# PDMschemE-Car2018.net
KiCad netlist of a schematic drawn in EAGLE
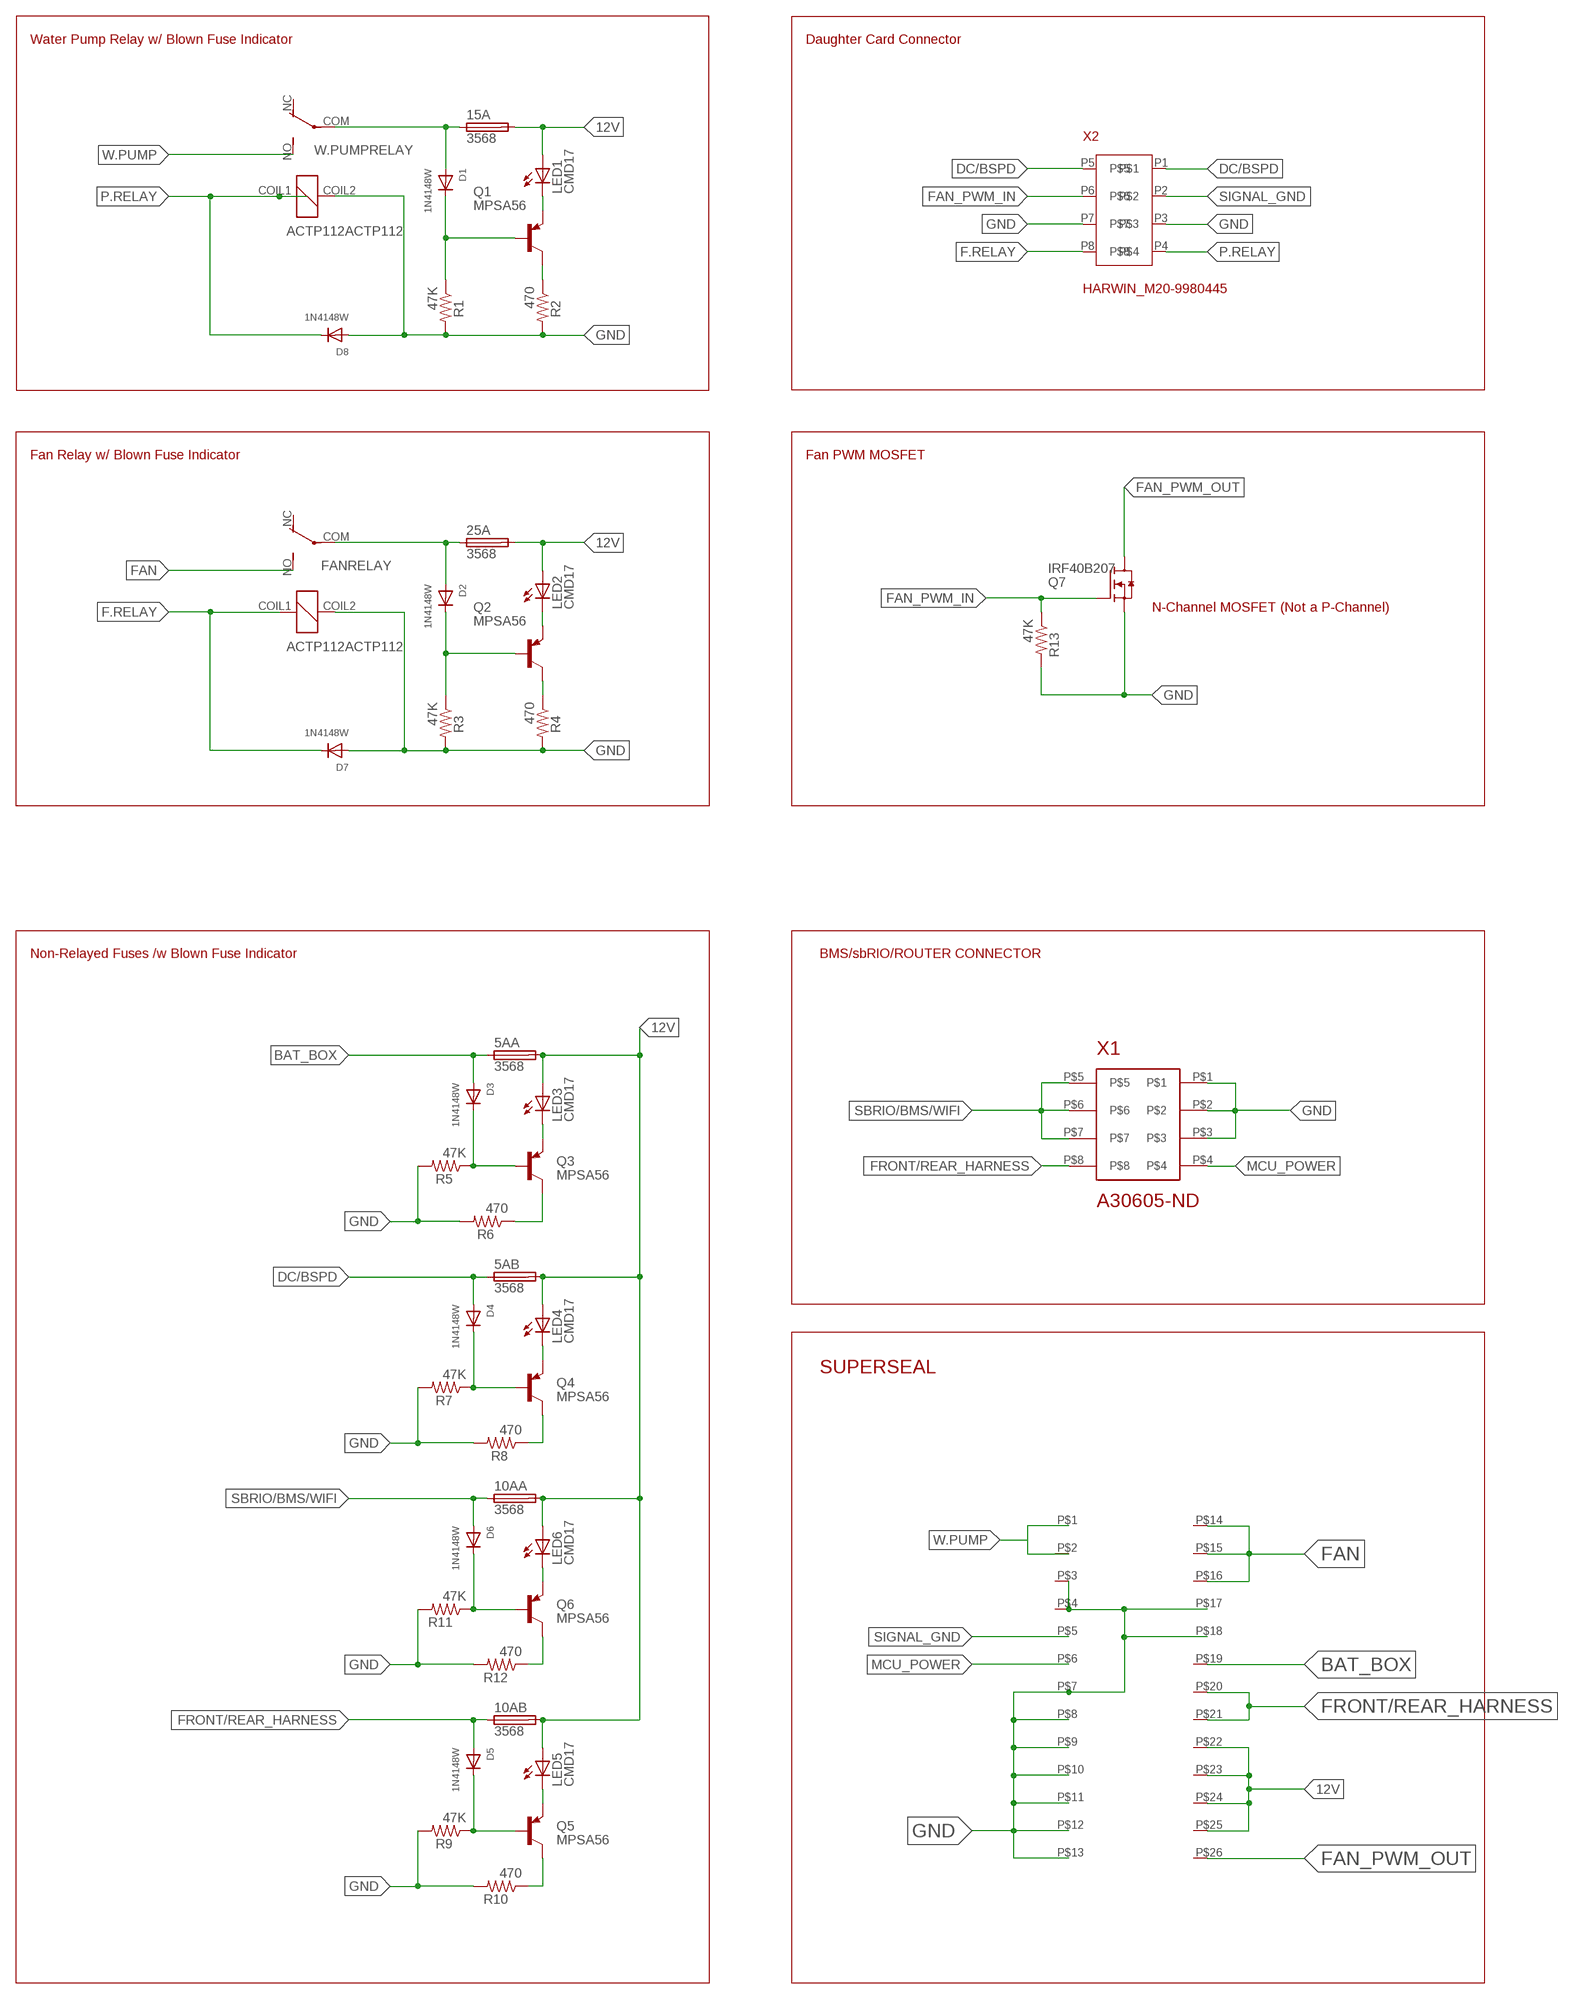
[diagram p0: schematic, sheet 1]

(export (version "E")
  (design (tool "Eeschema 10.0.6"))
  (components
    (comp (ref "5AA")
      (value "3568")
      (footprint "eagle-import:3568")
      (libsource (lib "eagle-import") (part "3568"))
    )
    (comp (ref "5AB")
      (value "3568")
      (footprint "eagle-import:3568")
      (libsource (lib "eagle-import") (part "3568"))
    )
    (comp (ref "10AA")
      (value "3568")
      (footprint "eagle-import:3568")
      (libsource (lib "eagle-import") (part "3568"))
    )
    (comp (ref "10AB")
      (value "3568")
      (footprint "eagle-import:3568")
      (libsource (lib "eagle-import") (part "3568"))
    )
    (comp (ref "15A")
      (value "3568")
      (footprint "eagle-import:3568")
      (libsource (lib "eagle-import") (part "3568"))
    )
    (comp (ref "25A")
      (value "3568")
      (footprint "eagle-import:3568")
      (libsource (lib "eagle-import") (part "3568"))
    )
    (comp (ref "D1")
      (value "1N4148W")
      (footprint "eagle-import:SOD-123")
      (libsource (lib "eagle-import") (part "DIODESOD-123"))
    )
    (comp (ref "D2")
      (value "1N4148W")
      (footprint "eagle-import:SOD-123")
      (libsource (lib "eagle-import") (part "DIODESOD-123"))
    )
    (comp (ref "D3")
      (value "1N4148W")
      (footprint "eagle-import:SOD-123")
      (libsource (lib "eagle-import") (part "DIODESOD-123"))
    )
    (comp (ref "D4")
      (value "1N4148W")
      (footprint "eagle-import:SOD-123")
      (libsource (lib "eagle-import") (part "DIODESOD-123"))
    )
    (comp (ref "D5")
      (value "1N4148W")
      (footprint "eagle-import:SOD-123")
      (libsource (lib "eagle-import") (part "DIODESOD-123"))
    )
    (comp (ref "D6")
      (value "1N4148W")
      (footprint "eagle-import:SOD-123")
      (libsource (lib "eagle-import") (part "DIODESOD-123"))
    )
    (comp (ref "D7")
      (value "1N4148W")
      (footprint "eagle-import:SOD-123")
      (libsource (lib "eagle-import") (part "DIODESOD-123"))
    )
    (comp (ref "D8")
      (value "1N4148W")
      (footprint "eagle-import:SOD-123")
      (libsource (lib "eagle-import") (part "DIODESOD-123"))
    )
    (comp (ref "FANRELAY")
      (value "ACTP112ACTP112")
      (footprint "eagle-import:ACTP112")
      (libsource (lib "eagle-import") (part "ACTP112ACTP112"))
    )
    (comp (ref "LED1")
      (value "CMD17")
      (footprint "eagle-import:CHIPLED_0805")
      (libsource (lib "eagle-import") (part "LEDCHIPLED_0805"))
    )
    (comp (ref "LED2")
      (value "CMD17")
      (footprint "eagle-import:CHIPLED_0805")
      (libsource (lib "eagle-import") (part "LEDCHIPLED_0805"))
    )
    (comp (ref "LED3")
      (value "CMD17")
      (footprint "eagle-import:CHIPLED_0805")
      (libsource (lib "eagle-import") (part "LEDCHIPLED_0805"))
    )
    (comp (ref "LED4")
      (value "CMD17")
      (footprint "eagle-import:CHIPLED_0805")
      (libsource (lib "eagle-import") (part "LEDCHIPLED_0805"))
    )
    (comp (ref "LED5")
      (value "CMD17")
      (footprint "eagle-import:CHIPLED_0805")
      (libsource (lib "eagle-import") (part "LEDCHIPLED_0805"))
    )
    (comp (ref "LED6")
      (value "CMD17")
      (footprint "eagle-import:CHIPLED_0805")
      (libsource (lib "eagle-import") (part "LEDCHIPLED_0805"))
    )
    (comp (ref "Q1")
      (value "MPSA56")
      (footprint "eagle-import:TO92-CBE")
      (libsource (lib "eagle-import") (part "MPSA56"))
    )
    (comp (ref "Q2")
      (value "MPSA56")
      (footprint "eagle-import:TO92-CBE")
      (libsource (lib "eagle-import") (part "MPSA56"))
    )
    (comp (ref "Q3")
      (value "MPSA56")
      (footprint "eagle-import:TO92-CBE")
      (libsource (lib "eagle-import") (part "MPSA56"))
    )
    (comp (ref "Q4")
      (value "MPSA56")
      (footprint "eagle-import:TO92-CBE")
      (libsource (lib "eagle-import") (part "MPSA56"))
    )
    (comp (ref "Q5")
      (value "MPSA56")
      (footprint "eagle-import:TO92-CBE")
      (libsource (lib "eagle-import") (part "MPSA56"))
    )
    (comp (ref "Q6")
      (value "MPSA56")
      (footprint "eagle-import:TO92-CBE")
      (libsource (lib "eagle-import") (part "MPSA56"))
    )
    (comp (ref "Q7")
      (value "IRF40B207")
      (footprint "eagle-import:TO220-3")
      (libsource (lib "eagle-import") (part "IRF40B207"))
    )
    (comp (ref "R1")
      (value "47K")
      (footprint "eagle-import:R1206")
      (libsource (lib "eagle-import") (part "R-US_R1206"))
    )
    (comp (ref "R2")
      (value "470")
      (footprint "eagle-import:R1206")
      (libsource (lib "eagle-import") (part "R-US_R1206"))
    )
    (comp (ref "R3")
      (value "47K")
      (footprint "eagle-import:R1206")
      (libsource (lib "eagle-import") (part "R-US_R1206"))
    )
    (comp (ref "R4")
      (value "470")
      (footprint "eagle-import:R1206")
      (libsource (lib "eagle-import") (part "R-US_R1206"))
    )
    (comp (ref "R5")
      (value "47K")
      (footprint "eagle-import:R1206")
      (libsource (lib "eagle-import") (part "R-US_R1206"))
    )
    (comp (ref "R6")
      (value "470")
      (footprint "eagle-import:R1206")
      (libsource (lib "eagle-import") (part "R-US_R1206"))
    )
    (comp (ref "R7")
      (value "47K")
      (footprint "eagle-import:R1206")
      (libsource (lib "eagle-import") (part "R-US_R1206"))
    )
    (comp (ref "R8")
      (value "470")
      (footprint "eagle-import:R1206")
      (libsource (lib "eagle-import") (part "R-US_R1206"))
    )
    (comp (ref "R9")
      (value "47K")
      (footprint "eagle-import:R1206")
      (libsource (lib "eagle-import") (part "R-US_R1206"))
    )
    (comp (ref "R10")
      (value "470")
      (footprint "eagle-import:R1206")
      (libsource (lib "eagle-import") (part "R-US_R1206"))
    )
    (comp (ref "R11")
      (value "47K")
      (footprint "eagle-import:R1206")
      (libsource (lib "eagle-import") (part "R-US_R1206"))
    )
    (comp (ref "R12")
      (value "470")
      (footprint "eagle-import:R1206")
      (libsource (lib "eagle-import") (part "R-US_R1206"))
    )
    (comp (ref "R13")
      (value "47K")
      (footprint "eagle-import:R1206")
      (libsource (lib "eagle-import") (part "R-US_R1206"))
    )
    (comp (ref "U$4")
      (value "SUPERSEAL1.0_26POS_2ROW")
      (footprint "eagle-import:SUPERSEAL1.0_26POS_2ROW")
      (libsource (lib "eagle-import") (part "SUPERSEAL1.0_26POS_2ROW"))
    )
    (comp (ref "W.PUMPRELAY")
      (value "ACTP112ACTP112")
      (footprint "eagle-import:ACTP112")
      (libsource (lib "eagle-import") (part "ACTP112ACTP112"))
    )
    (comp (ref "X1")
      (value "A30605-ND")
      (footprint "eagle-import:A30605-ND")
      (libsource (lib "eagle-import") (part "A30605-ND"))
    )
    (comp (ref "X2")
      (value "HARWIN_M20-9980445")
      (footprint "eagle-import:HARWIN_M20-9980445")
      (libsource (lib "eagle-import") (part "HARWIN_M20-9980445"))
    )
  )
  (nets
    (net (code "1") (name "12V") (class "Default")
      (node (ref "10AA") (pin "3") (pinfunction "2_3") (pintype "passive"))
      (node (ref "10AA") (pin "4") (pinfunction "2_4") (pintype "passive"))
      (node (ref "10AB") (pin "3") (pinfunction "2_3") (pintype "passive"))
      (node (ref "10AB") (pin "4") (pinfunction "2_4") (pintype "passive"))
      (node (ref "15A") (pin "3") (pinfunction "2_3") (pintype "passive"))
      (node (ref "15A") (pin "4") (pinfunction "2_4") (pintype "passive"))
      (node (ref "25A") (pin "3") (pinfunction "2_3") (pintype "passive"))
      (node (ref "25A") (pin "4") (pinfunction "2_4") (pintype "passive"))
      (node (ref "5AA") (pin "3") (pinfunction "2_3") (pintype "passive"))
      (node (ref "5AA") (pin "4") (pinfunction "2_4") (pintype "passive"))
      (node (ref "5AB") (pin "3") (pinfunction "2_3") (pintype "passive"))
      (node (ref "5AB") (pin "4") (pinfunction "2_4") (pintype "passive"))
      (node (ref "LED1") (pin "A") (pinfunction "A_A") (pintype "passive"))
      (node (ref "LED2") (pin "A") (pinfunction "A_A") (pintype "passive"))
      (node (ref "LED3") (pin "A") (pinfunction "A_A") (pintype "passive"))
      (node (ref "LED4") (pin "A") (pinfunction "A_A") (pintype "passive"))
      (node (ref "LED5") (pin "A") (pinfunction "A_A") (pintype "passive"))
      (node (ref "LED6") (pin "A") (pinfunction "A_A") (pintype "passive"))
      (node (ref "U$4") (pin "P$22") (pinfunction "B22_P$22") (pintype "bidirectional"))
      (node (ref "U$4") (pin "P$23") (pinfunction "B23_P$23") (pintype "bidirectional"))
      (node (ref "U$4") (pin "P$24") (pinfunction "B24_P$24") (pintype "bidirectional"))
      (node (ref "U$4") (pin "P$25") (pinfunction "B25_P$25") (pintype "bidirectional"))
    )
    (net (code "2") (name "BAT_BOX") (class "Default")
      (node (ref "5AA") (pin "1") (pinfunction "1_1") (pintype "passive"))
      (node (ref "5AA") (pin "2") (pinfunction "1_2") (pintype "passive"))
      (node (ref "D3") (pin "A") (pinfunction "A_A") (pintype "passive"))
      (node (ref "U$4") (pin "P$19") (pinfunction "B19_P$19") (pintype "bidirectional"))
    )
    (net (code "3") (name "DC{slash}BSPD") (class "Default")
      (node (ref "5AB") (pin "1") (pinfunction "1_1") (pintype "passive"))
      (node (ref "5AB") (pin "2") (pinfunction "1_2") (pintype "passive"))
      (node (ref "D4") (pin "A") (pinfunction "A_A") (pintype "passive"))
      (node (ref "X2") (pin "P1") (pinfunction "P$1_P1") (pintype "bidirectional"))
      (node (ref "X2") (pin "P5") (pinfunction "P$5_P5") (pintype "bidirectional"))
    )
    (net (code "4") (name "F.RELAY") (class "Default")
      (node (ref "D7") (pin "C") (pinfunction "C_C") (pintype "passive"))
      (node (ref "FANRELAY") (pin "COIL1") (pinfunction "COIL1_COIL1") (pintype "passive"))
      (node (ref "X2") (pin "P8") (pinfunction "P$8_P8") (pintype "bidirectional"))
    )
    (net (code "5") (name "FAN") (class "Default")
      (node (ref "FANRELAY") (pin "NO") (pinfunction "NO_NO") (pintype "passive"))
      (node (ref "U$4") (pin "P$14") (pinfunction "B14_P$14") (pintype "bidirectional"))
      (node (ref "U$4") (pin "P$15") (pinfunction "B15_P$15") (pintype "bidirectional"))
      (node (ref "U$4") (pin "P$16") (pinfunction "B16_P$16") (pintype "bidirectional"))
    )
    (net (code "6") (name "FAN_PWM_IN") (class "Default")
      (node (ref "Q7") (pin "G") (pinfunction "G_G") (pintype "passive"))
      (node (ref "R13") (pin "1") (pinfunction "1_1") (pintype "passive"))
      (node (ref "X2") (pin "P6") (pinfunction "P$6_P6") (pintype "bidirectional"))
    )
    (net (code "7") (name "FAN_PWM_OUT") (class "Default")
      (node (ref "Q7") (pin "D") (pinfunction "D_D") (pintype "passive"))
      (node (ref "U$4") (pin "P$26") (pinfunction "B26_P$26") (pintype "bidirectional"))
    )
    (net (code "8") (name "FRONT{slash}REAR_HARNESS") (class "Default")
      (node (ref "10AB") (pin "1") (pinfunction "1_1") (pintype "passive"))
      (node (ref "10AB") (pin "2") (pinfunction "1_2") (pintype "passive"))
      (node (ref "D5") (pin "A") (pinfunction "A_A") (pintype "passive"))
      (node (ref "U$4") (pin "P$20") (pinfunction "B20_P$20") (pintype "bidirectional"))
      (node (ref "U$4") (pin "P$21") (pinfunction "B21_P$21") (pintype "bidirectional"))
      (node (ref "X1") (pin "P$8") (pinfunction "P$8_P$8") (pintype "bidirectional"))
    )
    (net (code "9") (name "GND") (class "Default")
      (node (ref "D7") (pin "A") (pinfunction "A_A") (pintype "passive"))
      (node (ref "D8") (pin "A") (pinfunction "A_A") (pintype "passive"))
      (node (ref "FANRELAY") (pin "COIL2") (pinfunction "COIL2_COIL2") (pintype "passive"))
      (node (ref "Q7") (pin "S") (pinfunction "S_S") (pintype "passive"))
      (node (ref "R1") (pin "2") (pinfunction "2_2") (pintype "passive"))
      (node (ref "R10") (pin "2") (pinfunction "2_2") (pintype "passive"))
      (node (ref "R11") (pin "2") (pinfunction "2_2") (pintype "passive"))
      (node (ref "R12") (pin "2") (pinfunction "2_2") (pintype "passive"))
      (node (ref "R13") (pin "2") (pinfunction "2_2") (pintype "passive"))
      (node (ref "R2") (pin "2") (pinfunction "2_2") (pintype "passive"))
      (node (ref "R3") (pin "2") (pinfunction "2_2") (pintype "passive"))
      (node (ref "R4") (pin "2") (pinfunction "2_2") (pintype "passive"))
      (node (ref "R5") (pin "2") (pinfunction "2_2") (pintype "passive"))
      (node (ref "R6") (pin "2") (pinfunction "2_2") (pintype "passive"))
      (node (ref "R7") (pin "2") (pinfunction "2_2") (pintype "passive"))
      (node (ref "R8") (pin "2") (pinfunction "2_2") (pintype "passive"))
      (node (ref "R9") (pin "2") (pinfunction "2_2") (pintype "passive"))
      (node (ref "U$4") (pin "P$10") (pinfunction "B10_P$10") (pintype "bidirectional"))
      (node (ref "U$4") (pin "P$11") (pinfunction "B11_P$11") (pintype "bidirectional"))
      (node (ref "U$4") (pin "P$12") (pinfunction "B12_P$12") (pintype "bidirectional"))
      (node (ref "U$4") (pin "P$13") (pinfunction "B13_P$13") (pintype "bidirectional"))
      (node (ref "U$4") (pin "P$17") (pinfunction "B17_P$17") (pintype "bidirectional"))
      (node (ref "U$4") (pin "P$18") (pinfunction "B18_P$18") (pintype "bidirectional"))
      (node (ref "U$4") (pin "P$3") (pinfunction "B3_P$3") (pintype "bidirectional"))
      (node (ref "U$4") (pin "P$4") (pinfunction "B4_P$4") (pintype "bidirectional"))
      (node (ref "U$4") (pin "P$7") (pinfunction "B7_P$7") (pintype "bidirectional"))
      (node (ref "U$4") (pin "P$8") (pinfunction "B8_P$8") (pintype "bidirectional"))
      (node (ref "U$4") (pin "P$9") (pinfunction "B9_P$9") (pintype "bidirectional"))
      (node (ref "W.PUMPRELAY") (pin "COIL2") (pinfunction "COIL2_COIL2") (pintype "passive"))
      (node (ref "X1") (pin "P$1") (pinfunction "P$1_P$1") (pintype "bidirectional"))
      (node (ref "X1") (pin "P$2") (pinfunction "P$2_P$2") (pintype "bidirectional"))
      (node (ref "X1") (pin "P$3") (pinfunction "P$3_P$3") (pintype "bidirectional"))
      (node (ref "X2") (pin "P3") (pinfunction "P$3_P3") (pintype "bidirectional"))
      (node (ref "X2") (pin "P7") (pinfunction "P$7_P7") (pintype "bidirectional"))
    )
    (net (code "10") (name "MCU_POWER") (class "Default")
      (node (ref "U$4") (pin "P$6") (pinfunction "B6_P$6") (pintype "bidirectional"))
      (node (ref "X1") (pin "P$4") (pinfunction "P$4_P$4") (pintype "bidirectional"))
    )
    (net (code "11") (name "Net-(15A-1-Pad2)") (class "Default")
      (node (ref "15A") (pin "1") (pinfunction "1_1") (pintype "passive"))
      (node (ref "15A") (pin "2") (pinfunction "1_2") (pintype "passive"))
      (node (ref "D1") (pin "A") (pinfunction "A_A") (pintype "passive"))
      (node (ref "W.PUMPRELAY") (pin "COM") (pinfunction "COM_COM") (pintype "passive"))
    )
    (net (code "12") (name "Net-(25A-1-Pad2)") (class "Default")
      (node (ref "25A") (pin "1") (pinfunction "1_1") (pintype "passive"))
      (node (ref "25A") (pin "2") (pinfunction "1_2") (pintype "passive"))
      (node (ref "D2") (pin "A") (pinfunction "A_A") (pintype "passive"))
      (node (ref "FANRELAY") (pin "COM") (pinfunction "COM_COM") (pintype "passive"))
    )
    (net (code "13") (name "Net-(D1-PadC)") (class "Default")
      (node (ref "D1") (pin "C") (pinfunction "C_C") (pintype "passive"))
      (node (ref "Q1") (pin "B") (pinfunction "B_B") (pintype "passive"))
      (node (ref "R1") (pin "1") (pinfunction "1_1") (pintype "passive"))
    )
    (net (code "14") (name "Net-(D2-PadC)") (class "Default")
      (node (ref "D2") (pin "C") (pinfunction "C_C") (pintype "passive"))
      (node (ref "Q2") (pin "B") (pinfunction "B_B") (pintype "passive"))
      (node (ref "R3") (pin "1") (pinfunction "1_1") (pintype "passive"))
    )
    (net (code "15") (name "Net-(D3-PadC)") (class "Default")
      (node (ref "D3") (pin "C") (pinfunction "C_C") (pintype "passive"))
      (node (ref "Q3") (pin "B") (pinfunction "B_B") (pintype "passive"))
      (node (ref "R5") (pin "1") (pinfunction "1_1") (pintype "passive"))
    )
    (net (code "16") (name "Net-(D4-PadC)") (class "Default")
      (node (ref "D4") (pin "C") (pinfunction "C_C") (pintype "passive"))
      (node (ref "Q4") (pin "B") (pinfunction "B_B") (pintype "passive"))
      (node (ref "R7") (pin "1") (pinfunction "1_1") (pintype "passive"))
    )
    (net (code "17") (name "Net-(D5-PadC)") (class "Default")
      (node (ref "D5") (pin "C") (pinfunction "C_C") (pintype "passive"))
      (node (ref "Q5") (pin "B") (pinfunction "B_B") (pintype "passive"))
      (node (ref "R9") (pin "1") (pinfunction "1_1") (pintype "passive"))
    )
    (net (code "18") (name "Net-(D6-PadC)") (class "Default")
      (node (ref "D6") (pin "C") (pinfunction "C_C") (pintype "passive"))
      (node (ref "Q6") (pin "B") (pinfunction "B_B") (pintype "passive"))
      (node (ref "R11") (pin "1") (pinfunction "1_1") (pintype "passive"))
    )
    (net (code "19") (name "Net-(LED1-PadC)") (class "Default")
      (node (ref "LED1") (pin "C") (pinfunction "C_C") (pintype "passive"))
      (node (ref "Q1") (pin "E") (pinfunction "E_E") (pintype "passive"))
    )
    (net (code "20") (name "Net-(LED2-PadC)") (class "Default")
      (node (ref "LED2") (pin "C") (pinfunction "C_C") (pintype "passive"))
      (node (ref "Q2") (pin "E") (pinfunction "E_E") (pintype "passive"))
    )
    (net (code "21") (name "Net-(LED3-PadC)") (class "Default")
      (node (ref "LED3") (pin "C") (pinfunction "C_C") (pintype "passive"))
      (node (ref "Q3") (pin "E") (pinfunction "E_E") (pintype "passive"))
    )
    (net (code "22") (name "Net-(LED4-PadC)") (class "Default")
      (node (ref "LED4") (pin "C") (pinfunction "C_C") (pintype "passive"))
      (node (ref "Q4") (pin "E") (pinfunction "E_E") (pintype "passive"))
    )
    (net (code "23") (name "Net-(LED5-PadC)") (class "Default")
      (node (ref "LED5") (pin "C") (pinfunction "C_C") (pintype "passive"))
      (node (ref "Q5") (pin "E") (pinfunction "E_E") (pintype "passive"))
    )
    (net (code "24") (name "Net-(LED6-PadC)") (class "Default")
      (node (ref "LED6") (pin "C") (pinfunction "C_C") (pintype "passive"))
      (node (ref "Q6") (pin "E") (pinfunction "E_E") (pintype "passive"))
    )
    (net (code "25") (name "Net-(Q1-PadC)") (class "Default")
      (node (ref "Q1") (pin "C") (pinfunction "C_C") (pintype "passive"))
      (node (ref "R2") (pin "1") (pinfunction "1_1") (pintype "passive"))
    )
    (net (code "26") (name "Net-(Q2-PadC)") (class "Default")
      (node (ref "Q2") (pin "C") (pinfunction "C_C") (pintype "passive"))
      (node (ref "R4") (pin "1") (pinfunction "1_1") (pintype "passive"))
    )
    (net (code "27") (name "Net-(Q3-PadC)") (class "Default")
      (node (ref "Q3") (pin "C") (pinfunction "C_C") (pintype "passive"))
      (node (ref "R6") (pin "1") (pinfunction "1_1") (pintype "passive"))
    )
    (net (code "28") (name "Net-(Q4-PadC)") (class "Default")
      (node (ref "Q4") (pin "C") (pinfunction "C_C") (pintype "passive"))
      (node (ref "R8") (pin "1") (pinfunction "1_1") (pintype "passive"))
    )
    (net (code "29") (name "Net-(Q5-PadC)") (class "Default")
      (node (ref "Q5") (pin "C") (pinfunction "C_C") (pintype "passive"))
      (node (ref "R10") (pin "1") (pinfunction "1_1") (pintype "passive"))
    )
    (net (code "30") (name "Net-(Q6-PadC)") (class "Default")
      (node (ref "Q6") (pin "C") (pinfunction "C_C") (pintype "passive"))
      (node (ref "R12") (pin "1") (pinfunction "1_1") (pintype "passive"))
    )
    (net (code "31") (name "P.RELAY") (class "Default")
      (node (ref "D8") (pin "C") (pinfunction "C_C") (pintype "passive"))
      (node (ref "W.PUMPRELAY") (pin "COIL1") (pinfunction "COIL1_COIL1") (pintype "passive"))
      (node (ref "X2") (pin "P4") (pinfunction "P$4_P4") (pintype "bidirectional"))
    )
    (net (code "32") (name "SBRIO{slash}BMS{slash}WIFI") (class "Default")
      (node (ref "10AA") (pin "1") (pinfunction "1_1") (pintype "passive"))
      (node (ref "10AA") (pin "2") (pinfunction "1_2") (pintype "passive"))
      (node (ref "D6") (pin "A") (pinfunction "A_A") (pintype "passive"))
      (node (ref "X1") (pin "P$5") (pinfunction "P$5_P$5") (pintype "bidirectional"))
      (node (ref "X1") (pin "P$6") (pinfunction "P$6_P$6") (pintype "bidirectional"))
      (node (ref "X1") (pin "P$7") (pinfunction "P$7_P$7") (pintype "bidirectional"))
    )
    (net (code "33") (name "SIGNAL_GND") (class "Default")
      (node (ref "U$4") (pin "P$5") (pinfunction "B5_P$5") (pintype "bidirectional"))
      (node (ref "X2") (pin "P2") (pinfunction "P$2_P2") (pintype "bidirectional"))
    )
    (net (code "34") (name "W.PUMP") (class "Default")
      (node (ref "U$4") (pin "P$1") (pinfunction "B1_P$1") (pintype "bidirectional"))
      (node (ref "U$4") (pin "P$2") (pinfunction "B2_P$2") (pintype "bidirectional"))
      (node (ref "W.PUMPRELAY") (pin "NO") (pinfunction "NO_NO") (pintype "passive"))
    )
    (net (code "35") (name "unconnected-(FANRELAY-PadNC)") (class "Default")
      (node (ref "FANRELAY") (pin "NC") (pinfunction "NC_NC") (pintype "passive"))
    )
    (net (code "36") (name "unconnected-(W.PUMPRELAY-PadNC)") (class "Default")
      (node (ref "W.PUMPRELAY") (pin "NC") (pinfunction "NC_NC") (pintype "passive"))
    )
  )
)
